# Power.net
KiCad netlist of a schematic drawn in Altium Designer
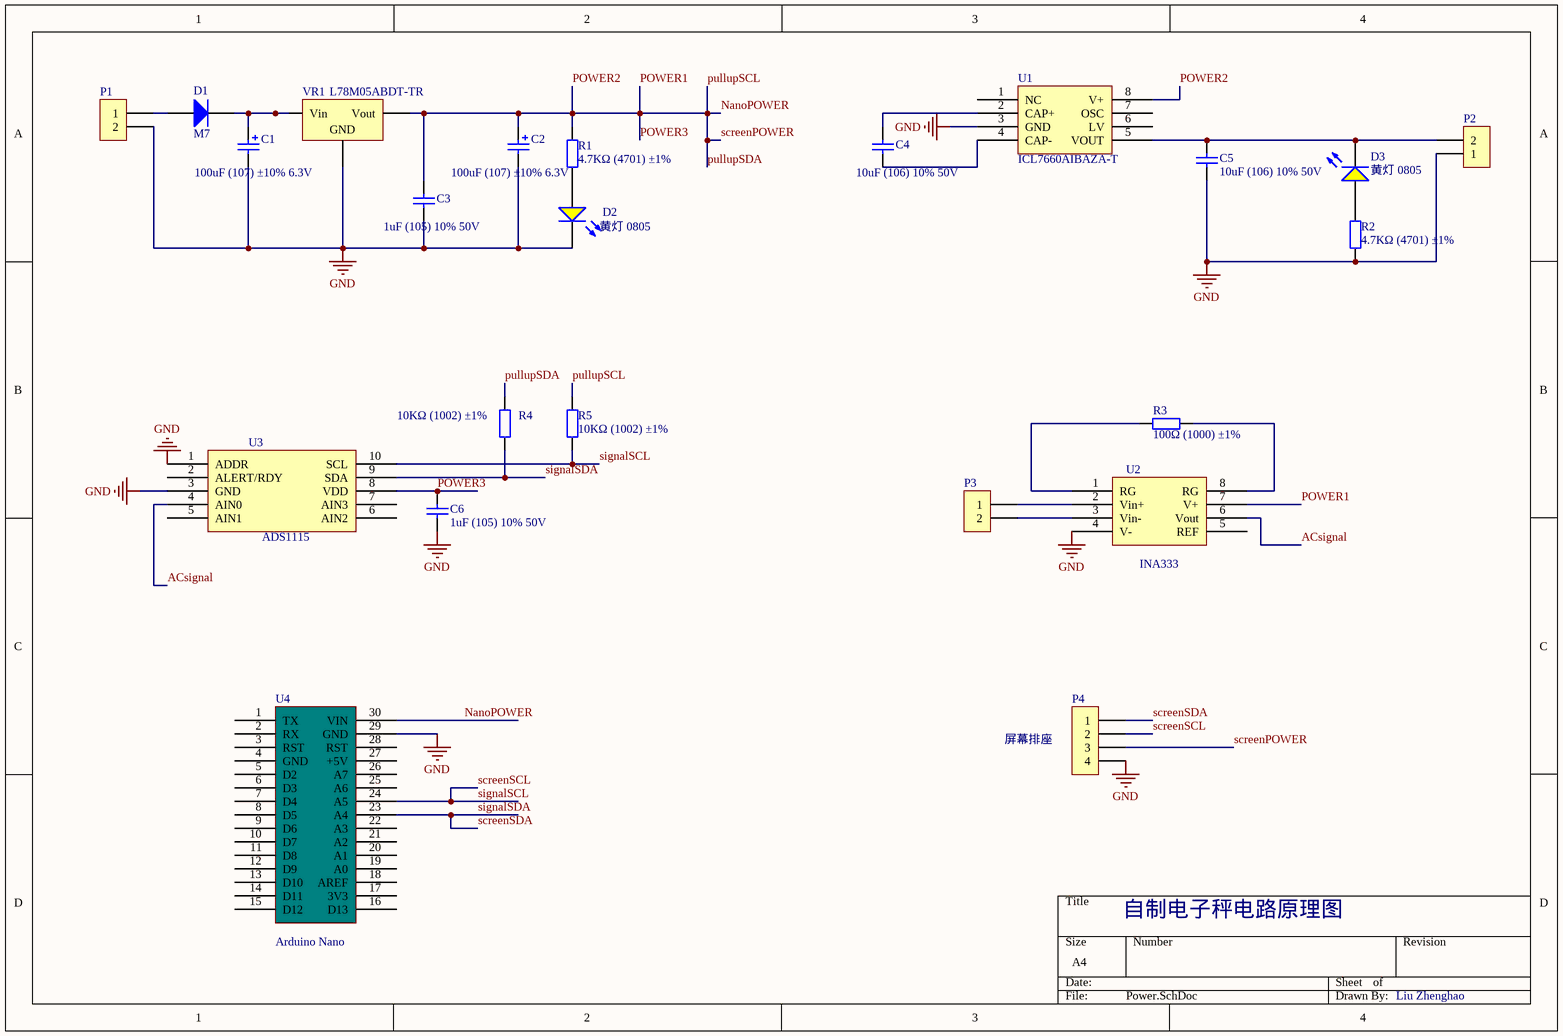
[diagram p0: Power.SchDoc]

(export (version "E")
  (design (tool "Eeschema 10.0.6"))
  (components
    (comp (ref "C1")
      (value "100uF (107) ±10% 6.3V")
      (footprint "LC-CASE-B_3528")
      (description "钽电容")
      (libsource (lib "Miscellaneous Devices LC") (part "3528 100uF (107) 10% 6.3V"))
    )
    (comp (ref "C2")
      (value "100uF (107) ±10% 6.3V")
      (footprint "LC-CASE-B_3528")
      (description "钽电容")
      (libsource (lib "Miscellaneous Devices LC") (part "3528 100uF (107) 10% 6.3V"))
    )
    (comp (ref "C3")
      (value "1uF (105) 10% 50V")
      (footprint "LC-1206_C")
      (description "贴片电容")
      (libsource (lib "Miscellaneous Devices LC") (part "1206 1uF (105) 10% 50V"))
    )
    (comp (ref "C4")
      (value "10uF (106) 10% 50V")
      (footprint "LC-1206_C")
      (description "贴片电容")
      (libsource (lib "Miscellaneous Devices LC") (part "1206 10uF (106) 10% 50V"))
    )
    (comp (ref "C5")
      (value "10uF (106) 10% 50V")
      (footprint "LC-1206_C")
      (description "贴片电容")
      (libsource (lib "Miscellaneous Devices LC") (part "1206 10uF (106) 10% 50V"))
    )
    (comp (ref "C6")
      (value "1uF (105) 10% 50V")
      (footprint "LC-1206_C")
      (description "贴片电容")
      (libsource (lib "Miscellaneous Devices LC") (part "1206 1uF (105) 10% 50V"))
    )
    (comp (ref "D1")
      (value "M7")
      (footprint "LC-SMA(DO-214AC)_S1")
      (description "二极管")
      (libsource (lib "Miscellaneous Devices LC") (part "SMA(DO-214AC) M7"))
    )
    (comp (ref "D2")
      (value "黄灯 0805")
      (footprint "LC-0805_LED_S1")
      (description "发光二极管")
      (libsource (lib "Miscellaneous Devices LC") (part "0805 黄灯"))
    )
    (comp (ref "D3")
      (value "黄灯 0805")
      (footprint "LC-0805_LED_S1")
      (description "发光二极管")
      (libsource (lib "Miscellaneous Devices LC") (part "0805 黄灯"))
    )
    (comp (ref "P1") (value "~") (footprint "Female1X2") (libsource (lib "") (part "排座与排针1X2_1")))
    (comp (ref "P2")
      (value "~")
      (footprint "Female1X2")
      (libsource (lib "党彤飞集成库（2017.4.3号更新）") (part "排座与排针1X2"))
    )
    (comp (ref "P3") (value "~") (footprint "Female1X2") (libsource (lib "") (part "排座与排针1X2_1")))
    (comp (ref "P4")
      (value "屏幕排座")
      (footprint "Female1X4")
      (libsource (lib "党彤飞集成库（2017.4.3号更新）") (part "排座与排针1X4"))
    )
    (comp (ref "R1")
      (value "4.7KΩ (4701) ±1%")
      (footprint "LC-1206_R")
      (description "贴片电阻")
      (libsource (lib "") (part "1206 4.7KΩ (4701) 1%_1"))
    )
    (comp (ref "R2")
      (value "4.7KΩ (4701) ±1%")
      (footprint "LC-1206_R")
      (description "贴片电阻")
      (libsource (lib "Miscellaneous Devices LC") (part "1206 4.7KΩ (4701) 1%"))
    )
    (comp (ref "R3")
      (value "100Ω (1000) ±1%")
      (footprint "LC-1206_R")
      (description "贴片电阻")
      (libsource (lib "Miscellaneous Devices LC") (part "1206 100Ω (1000) 1%"))
    )
    (comp (ref "R4")
      (value "10KΩ (1002) ±1%")
      (footprint "LC-1206_R")
      (description "贴片电阻")
      (libsource (lib "Miscellaneous Devices LC") (part "1206 10KΩ (1002) 1%"))
    )
    (comp (ref "R5")
      (value "10KΩ (1002) ±1%")
      (footprint "LC-1206_R")
      (description "贴片电阻")
      (libsource (lib "Miscellaneous Devices LC") (part "1206 10KΩ (1002) 1%"))
    )
    (comp (ref "U1")
      (value "ICL7660AIBAZA-T")
      (footprint "LC-SOIC-8_150mil")
      (description "电源芯片")
      (libsource (lib "Miscellaneous Devices LC") (part "ICL7660AIBAZA-T"))
    )
    (comp (ref "U2")
      (value "INA333")
      (footprint "VSSOP-8")
      (description "仪用放大器")
      (libsource (lib "*") (part "INA333"))
    )
    (comp (ref "U3") (value "ADS1115") (footprint "MSOP10") (libsource (lib "*") (part "ADS1115")))
    (comp (ref "U4")
      (value "Arduino Nano")
      (footprint "PCBComponent_1")
      (libsource (lib "Free Documents") (part "Component_1_1"))
    )
    (comp (ref "VR1")
      (value "L78M05ABDT-TR")
      (footprint "LC-TO-252-2-180")
      (description "低压差线性稳压(LDO)")
      (libsource (lib "Miscellaneous Devices LC") (part "TO-252-2 L78M05ABDT-TR"))
    )
  )
  (nets
    (net (code "1") (name "/ACsignal") (class "Default")
      (node (ref "U2") (pin "6") (pinfunction "Vout_6") (pintype "passive"))
      (node (ref "U3") (pin "4") (pinfunction "AIN0_4") (pintype "passive"))
    )
    (net (code "2") (name "/NanoPOWER") (class "Default")
      (node (ref "C2") (pin "1") (pinfunction "1_1") (pintype "passive"))
      (node (ref "C3") (pin "2") (pinfunction "2_2") (pintype "passive"))
      (node (ref "C6") (pin "2") (pinfunction "2_2") (pintype "passive"))
      (node (ref "P4") (pin "3") (pinfunction "3_3") (pintype "passive"))
      (node (ref "R1") (pin "2") (pinfunction "2_2") (pintype "passive"))
      (node (ref "R4") (pin "2") (pinfunction "2_2") (pintype "passive"))
      (node (ref "R5") (pin "2") (pinfunction "2_2") (pintype "passive"))
      (node (ref "U1") (pin "8") (pinfunction "V+_8") (pintype "passive"))
      (node (ref "U2") (pin "7") (pinfunction "V+_7") (pintype "passive"))
      (node (ref "U3") (pin "8") (pinfunction "VDD_8") (pintype "passive"))
      (node (ref "U4") (pin "30") (pinfunction "VIN_30") (pintype "passive"))
      (node (ref "VR1") (pin "3") (pinfunction "Vout_3") (pintype "passive"))
    )
    (net (code "3") (name "/screenSCL") (class "Default")
      (node (ref "P4") (pin "2") (pinfunction "2_2") (pintype "passive"))
      (node (ref "R5") (pin "1") (pinfunction "1_1") (pintype "passive"))
      (node (ref "U3") (pin "10") (pinfunction "SCL_10") (pintype "passive"))
      (node (ref "U4") (pin "24") (pinfunction "A5_24") (pintype "passive"))
    )
    (net (code "4") (name "/screenSDA") (class "Default")
      (node (ref "P4") (pin "1") (pinfunction "1_1") (pintype "passive"))
      (node (ref "R4") (pin "1") (pinfunction "1_1") (pintype "passive"))
      (node (ref "U3") (pin "9") (pinfunction "SDA_9") (pintype "passive"))
      (node (ref "U4") (pin "23") (pinfunction "A4_23") (pintype "passive"))
    )
    (net (code "5") (name "GND") (class "Default")
      (node (ref "C1") (pin "2") (pinfunction "2_2") (pintype "passive"))
      (node (ref "C2") (pin "2") (pinfunction "2_2") (pintype "passive"))
      (node (ref "C3") (pin "1") (pinfunction "1_1") (pintype "passive"))
      (node (ref "C5") (pin "1") (pinfunction "1_1") (pintype "passive"))
      (node (ref "C6") (pin "1") (pinfunction "1_1") (pintype "passive"))
      (node (ref "D2") (pin "K") (pinfunction "K_K") (pintype "passive"))
      (node (ref "P1") (pin "2") (pinfunction "2_2") (pintype "passive"))
      (node (ref "P2") (pin "1") (pinfunction "1_1") (pintype "passive"))
      (node (ref "P4") (pin "4") (pinfunction "4_4") (pintype "passive"))
      (node (ref "R2") (pin "2") (pinfunction "2_2") (pintype "passive"))
      (node (ref "U1") (pin "3") (pinfunction "GND_3") (pintype "passive"))
      (node (ref "U2") (pin "4") (pinfunction "V-_4") (pintype "passive"))
      (node (ref "U3") (pin "1") (pinfunction "ADDR_1") (pintype "passive"))
      (node (ref "U3") (pin "3") (pinfunction "GND_3") (pintype "passive"))
      (node (ref "U4") (pin "29") (pinfunction "GND_29") (pintype "passive"))
      (node (ref "VR1") (pin "2") (pinfunction "GND_2") (pintype "passive"))
    )
    (net (code "6") (name "Net-(D1-A)") (class "Default")
      (node (ref "D1") (pin "1") (pinfunction "A_1") (pintype "passive"))
      (node (ref "P1") (pin "1") (pinfunction "1_1") (pintype "passive"))
    )
    (net (code "7") (name "Net-(D1-K)") (class "Default")
      (node (ref "C1") (pin "1") (pinfunction "1_1") (pintype "passive"))
      (node (ref "D1") (pin "2") (pinfunction "K_2") (pintype "passive"))
      (node (ref "VR1") (pin "1") (pinfunction "Vin_1") (pintype "passive"))
    )
    (net (code "8") (name "Net-(D2-PadA)") (class "Default")
      (node (ref "D2") (pin "A") (pinfunction "A_A") (pintype "passive"))
      (node (ref "R1") (pin "1") (pinfunction "1_1") (pintype "passive"))
    )
    (net (code "9") (name "Net-(D3-PadA)") (class "Default")
      (node (ref "D3") (pin "A") (pinfunction "A_A") (pintype "passive"))
      (node (ref "R2") (pin "1") (pinfunction "1_1") (pintype "passive"))
    )
    (net (code "10") (name "Net-(R3-Pad1)") (class "Default")
      (node (ref "R3") (pin "1") (pinfunction "1_1") (pintype "passive"))
      (node (ref "U2") (pin "1") (pinfunction "RG_1") (pintype "passive"))
    )
    (net (code "11") (name "Net-(R3-Pad2)") (class "Default")
      (node (ref "R3") (pin "2") (pinfunction "2_2") (pintype "passive"))
      (node (ref "U2") (pin "8") (pinfunction "RG_8") (pintype "passive"))
    )
    (net (code "12") (name "Net-(U1-CAP+)") (class "Default")
      (node (ref "C4") (pin "2") (pinfunction "2_2") (pintype "passive"))
      (node (ref "U1") (pin "2") (pinfunction "CAP+_2") (pintype "passive"))
    )
    (net (code "13") (name "Net-(U1-CAP-)") (class "Default")
      (node (ref "C4") (pin "1") (pinfunction "1_1") (pintype "passive"))
      (node (ref "U1") (pin "4") (pinfunction "CAP-_4") (pintype "passive"))
    )
    (net (code "14") (name "Net-(U1-VOUT)") (class "Default")
      (node (ref "C5") (pin "2") (pinfunction "2_2") (pintype "passive"))
      (node (ref "D3") (pin "K") (pinfunction "K_K") (pintype "passive"))
      (node (ref "P2") (pin "2") (pinfunction "2_2") (pintype "passive"))
      (node (ref "U1") (pin "5") (pinfunction "VOUT_5") (pintype "passive"))
    )
    (net (code "15") (name "Net-(U2-Vin+)") (class "Default")
      (node (ref "P3") (pin "1") (pinfunction "1_1") (pintype "passive"))
      (node (ref "U2") (pin "2") (pinfunction "Vin+_2") (pintype "passive"))
    )
    (net (code "16") (name "Net-(U2-Vin-)") (class "Default")
      (node (ref "P3") (pin "2") (pinfunction "2_2") (pintype "passive"))
      (node (ref "U2") (pin "3") (pinfunction "Vin-_3") (pintype "passive"))
    )
    (net (code "17") (name "unconnected-(U1-LV-Pad6)") (class "Default")
      (node (ref "U1") (pin "6") (pinfunction "LV_6") (pintype "passive"))
    )
    (net (code "18") (name "unconnected-(U1-NC-Pad1)") (class "Default")
      (node (ref "U1") (pin "1") (pinfunction "NC_1") (pintype "passive"))
    )
    (net (code "19") (name "unconnected-(U1-OSC-Pad7)") (class "Default")
      (node (ref "U1") (pin "7") (pinfunction "OSC_7") (pintype "passive"))
    )
    (net (code "20") (name "unconnected-(U2-REF-Pad5)") (class "Default")
      (node (ref "U2") (pin "5") (pinfunction "REF_5") (pintype "passive"))
    )
    (net (code "21") (name "unconnected-(U3-AIN1-Pad5)") (class "Default")
      (node (ref "U3") (pin "5") (pinfunction "AIN1_5") (pintype "passive"))
    )
    (net (code "22") (name "unconnected-(U3-AIN2-Pad6)") (class "Default")
      (node (ref "U3") (pin "6") (pinfunction "AIN2_6") (pintype "passive"))
    )
    (net (code "23") (name "unconnected-(U3-AIN3-Pad7)") (class "Default")
      (node (ref "U3") (pin "7") (pinfunction "AIN3_7") (pintype "passive"))
    )
    (net (code "24") (name "unconnected-(U3-ALERT{slash}RDY-Pad2)") (class "Default")
      (node (ref "U3") (pin "2") (pinfunction "ALERT/RDY_2") (pintype "passive"))
    )
    (net (code "25") (name "unconnected-(U4-+5V-Pad27)") (class "Default")
      (node (ref "U4") (pin "27") (pinfunction "+5V_27") (pintype "passive"))
    )
    (net (code "26") (name "unconnected-(U4-3V3-Pad17)") (class "Default")
      (node (ref "U4") (pin "17") (pinfunction "3V3_17") (pintype "passive"))
    )
    (net (code "27") (name "unconnected-(U4-A0-Pad19)") (class "Default")
      (node (ref "U4") (pin "19") (pinfunction "A0_19") (pintype "passive"))
    )
    (net (code "28") (name "unconnected-(U4-A1-Pad20)") (class "Default")
      (node (ref "U4") (pin "20") (pinfunction "A1_20") (pintype "passive"))
    )
    (net (code "29") (name "unconnected-(U4-A2-Pad21)") (class "Default")
      (node (ref "U4") (pin "21") (pinfunction "A2_21") (pintype "passive"))
    )
    (net (code "30") (name "unconnected-(U4-A3-Pad22)") (class "Default")
      (node (ref "U4") (pin "22") (pinfunction "A3_22") (pintype "passive"))
    )
    (net (code "31") (name "unconnected-(U4-A6-Pad25)") (class "Default")
      (node (ref "U4") (pin "25") (pinfunction "A6_25") (pintype "passive"))
    )
    (net (code "32") (name "unconnected-(U4-A7-Pad26)") (class "Default")
      (node (ref "U4") (pin "26") (pinfunction "A7_26") (pintype "passive"))
    )
    (net (code "33") (name "unconnected-(U4-AREF-Pad18)") (class "Default")
      (node (ref "U4") (pin "18") (pinfunction "AREF_18") (pintype "passive"))
    )
    (net (code "34") (name "unconnected-(U4-D2-Pad5)") (class "Default")
      (node (ref "U4") (pin "5") (pinfunction "D2_5") (pintype "passive"))
    )
    (net (code "35") (name "unconnected-(U4-D3-Pad6)") (class "Default")
      (node (ref "U4") (pin "6") (pinfunction "D3_6") (pintype "passive"))
    )
    (net (code "36") (name "unconnected-(U4-D4-Pad7)") (class "Default")
      (node (ref "U4") (pin "7") (pinfunction "D4_7") (pintype "passive"))
    )
    (net (code "37") (name "unconnected-(U4-D5-Pad8)") (class "Default")
      (node (ref "U4") (pin "8") (pinfunction "D5_8") (pintype "passive"))
    )
    (net (code "38") (name "unconnected-(U4-D6-Pad9)") (class "Default")
      (node (ref "U4") (pin "9") (pinfunction "D6_9") (pintype "passive"))
    )
    (net (code "39") (name "unconnected-(U4-D7-Pad10)") (class "Default")
      (node (ref "U4") (pin "10") (pinfunction "D7_10") (pintype "passive"))
    )
    (net (code "40") (name "unconnected-(U4-D8-Pad11)") (class "Default")
      (node (ref "U4") (pin "11") (pinfunction "D8_11") (pintype "passive"))
    )
    (net (code "41") (name "unconnected-(U4-D9-Pad12)") (class "Default")
      (node (ref "U4") (pin "12") (pinfunction "D9_12") (pintype "passive"))
    )
    (net (code "42") (name "unconnected-(U4-D10-Pad13)") (class "Default")
      (node (ref "U4") (pin "13") (pinfunction "D10_13") (pintype "passive"))
    )
    (net (code "43") (name "unconnected-(U4-D11-Pad14)") (class "Default")
      (node (ref "U4") (pin "14") (pinfunction "D11_14") (pintype "passive"))
    )
    (net (code "44") (name "unconnected-(U4-D12-Pad15)") (class "Default")
      (node (ref "U4") (pin "15") (pinfunction "D12_15") (pintype "passive"))
    )
    (net (code "45") (name "unconnected-(U4-D13-Pad16)") (class "Default")
      (node (ref "U4") (pin "16") (pinfunction "D13_16") (pintype "passive"))
    )
    (net (code "46") (name "unconnected-(U4-GND-Pad4)") (class "Default")
      (node (ref "U4") (pin "4") (pinfunction "GND_4") (pintype "passive"))
    )
    (net (code "47") (name "unconnected-(U4-RST-Pad3)") (class "Default")
      (node (ref "U4") (pin "3") (pinfunction "RST_3") (pintype "passive"))
    )
    (net (code "48") (name "unconnected-(U4-RST-Pad28)") (class "Default")
      (node (ref "U4") (pin "28") (pinfunction "RST_28") (pintype "passive"))
    )
    (net (code "49") (name "unconnected-(U4-RX-Pad2)") (class "Default")
      (node (ref "U4") (pin "2") (pinfunction "RX_2") (pintype "passive"))
    )
    (net (code "50") (name "unconnected-(U4-TX-Pad1)") (class "Default")
      (node (ref "U4") (pin "1") (pinfunction "TX_1") (pintype "passive"))
    )
  )
)
